# MotorDriver.net
KiCad netlist of a schematic drawn in Altium Designer
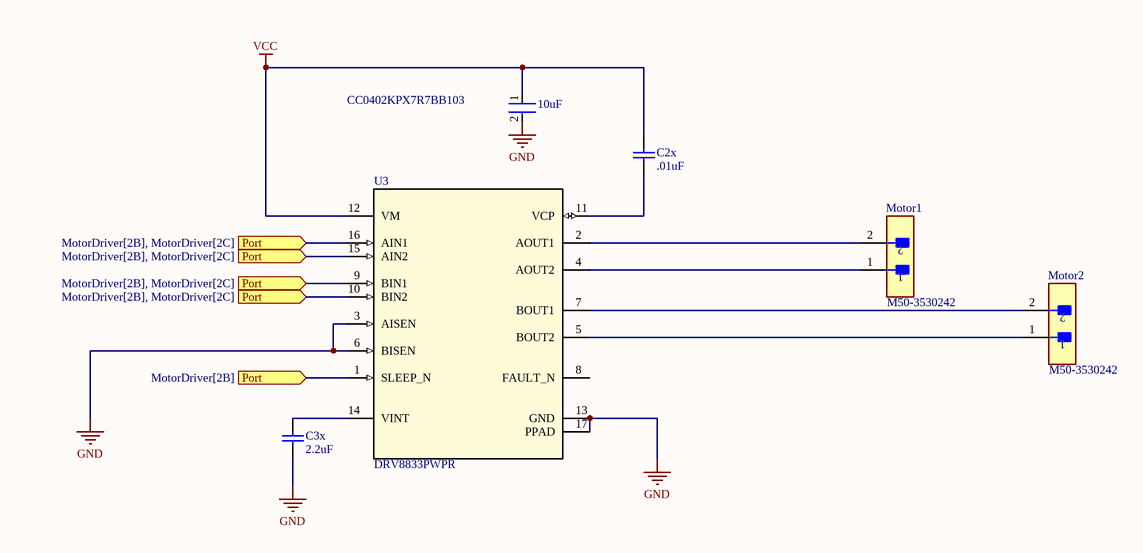
[diagram p0: MotorDriver.SchDoc]

(export (version "E")
  (design (tool "Eeschema 10.0.6"))
  (components
    (comp (ref "10uF")
      (value "CC0402KPX7R7BB103")
      (footprint "FP-CC0402-MFG")
      (description "CC0402 10 nF X7R 10.00% 16 V")
      (fields
        (field (name "TOLERANCE") "0.1")
        (field (name "OCTOPART") "https://octopart.com/cc0402kpx7r7bb103-yageo-12885102")
      )
      (libsource (lib "Altium Content Vault") (part "11868f565c42a9108669ba33697ecf6"))
    )
    (comp (ref "C2x")
      (value ".01uF")
      (description "Capacitor")
      (libsource (lib "Simulation Generic Components") (part "Capacitor"))
    )
    (comp (ref "C3x")
      (value "2.2uF")
      (description "Capacitor")
      (libsource (lib "Simulation Generic Components") (part "Capacitor"))
    )
    (comp (ref "Motor1")
      (value "M50-3530242")
      (footprint "FP-M50-3530242-MFG")
      (description "CONN HEADER VERT 2POS 1.27MM")
      (libsource (lib "Altium Content Vault") (part "3bc925449376181038e59eaffc5286c"))
    )
    (comp (ref "Motor2")
      (value "M50-3530242")
      (footprint "FP-M50-3530242-MFG")
      (description "CONN HEADER VERT 2POS 1.27MM")
      (libsource (lib "Altium Content Vault") (part "3bc925449376181038e59eaffc5286c"))
    )
    (comp (ref "U3")
      (value "DRV8833PWPR")
      (footprint "PWP0016C_N")
      (description "10.8-V, 2-A dual H-bridge motor driver with current regulation 16-HTSSOP -40 to 85")
      (fields (field (name "COPYRIGHT") "Copyright (C) 2025 Ultra Librarian. All rights reserved."))
      (libsource (lib "DRV8833PWPR") (part "DRV8833PWPR"))
    )
  )
  (nets
    (net (code "1") (name "/Port") (class "Default")
      (node (ref "U3") (pin "1") (pinfunction "SLEEP_N_1") (pintype "input"))
      (node (ref "U3") (pin "10") (pinfunction "BIN2_10") (pintype "input"))
      (node (ref "U3") (pin "15") (pinfunction "AIN2_15") (pintype "input"))
      (node (ref "U3") (pin "16") (pinfunction "AIN1_16") (pintype "input"))
      (node (ref "U3") (pin "9") (pinfunction "BIN1_9") (pintype "input"))
    )
    (net (code "2") (name "GND") (class "Default")
      (node (ref "10uF") (pin "2") (pinfunction "2_2") (pintype "passive"))
      (node (ref "C3x") (pin "1") (pinfunction "1_1") (pintype "passive"))
      (node (ref "U3") (pin "13") (pinfunction "GND_13") (pintype "power_in"))
      (node (ref "U3") (pin "17") (pinfunction "PPAD_17") (pintype "power_in"))
      (node (ref "U3") (pin "3") (pinfunction "AISEN_3") (pintype "input"))
      (node (ref "U3") (pin "6") (pinfunction "BISEN_6") (pintype "input"))
    )
    (net (code "3") (name "Net-(U3-AOUT1)") (class "Default")
      (node (ref "Motor1") (pin "2") (pinfunction "2_2") (pintype "passive"))
      (node (ref "U3") (pin "2") (pinfunction "AOUT1_2") (pintype "tri_state"))
    )
    (net (code "4") (name "Net-(U3-AOUT2)") (class "Default")
      (node (ref "Motor1") (pin "1") (pinfunction "1_1") (pintype "passive"))
      (node (ref "U3") (pin "4") (pinfunction "AOUT2_4") (pintype "tri_state"))
    )
    (net (code "5") (name "Net-(U3-BOUT1)") (class "Default")
      (node (ref "Motor2") (pin "2") (pinfunction "2_2") (pintype "passive"))
      (node (ref "U3") (pin "7") (pinfunction "BOUT1_7") (pintype "tri_state"))
    )
    (net (code "6") (name "Net-(U3-BOUT2)") (class "Default")
      (node (ref "Motor2") (pin "1") (pinfunction "1_1") (pintype "passive"))
      (node (ref "U3") (pin "5") (pinfunction "BOUT2_5") (pintype "tri_state"))
    )
    (net (code "7") (name "Net-(U3-VCP)") (class "Default")
      (node (ref "C2x") (pin "1") (pinfunction "1_1") (pintype "passive"))
      (node (ref "U3") (pin "11") (pinfunction "VCP_11") (pintype "bidirectional"))
    )
    (net (code "8") (name "Net-(U3-VINT)") (class "Default")
      (node (ref "C3x") (pin "2") (pinfunction "2_2") (pintype "passive"))
      (node (ref "U3") (pin "14") (pinfunction "VINT_14") (pintype "passive"))
    )
    (net (code "9") (name "VCC") (class "Default")
      (node (ref "10uF") (pin "1") (pinfunction "1_1") (pintype "passive"))
      (node (ref "C2x") (pin "2") (pinfunction "2_2") (pintype "passive"))
      (node (ref "U3") (pin "12") (pinfunction "VM_12") (pintype "power_in"))
    )
    (net (code "10") (name "unconnected-(U3-FAULT_N-Pad8)") (class "Default")
      (node (ref "U3") (pin "8") (pinfunction "FAULT_N_8") (pintype "open_collector"))
    )
  )
)
